# altmotor2.net
KiCad netlist of a schematic drawn in EAGLE
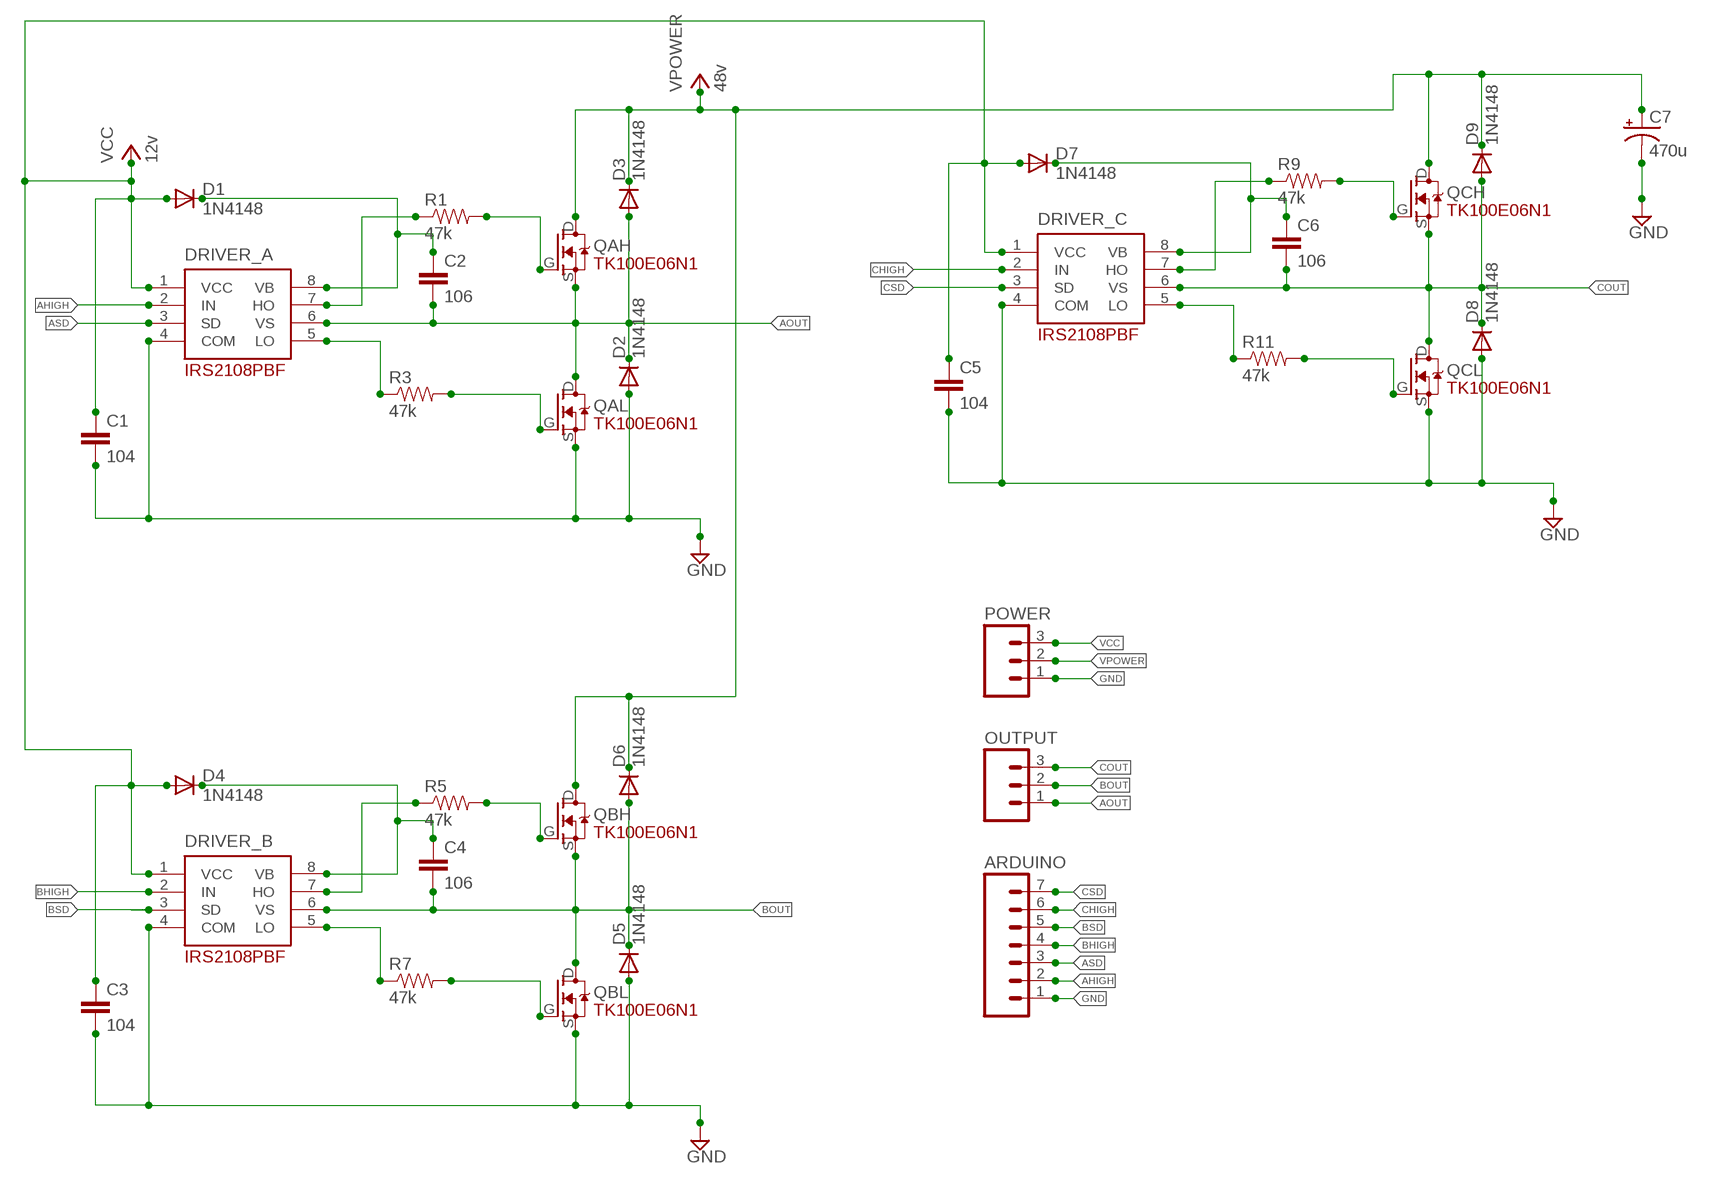
[diagram p0: schematic, sheet 1]

(export (version "E")
  (design (tool "Eeschema 10.0.6"))
  (components
    (comp (ref "ARDUINO")
      (value "M07LONGPADS")
      (footprint "eagle-import:1X07_LONGPADS")
      (libsource (lib "eagle-import") (part "M07LONGPADS"))
    )
    (comp (ref "C1")
      (value "104")
      (footprint "eagle-import:CAP-PTH-5MM")
      (libsource (lib "eagle-import") (part "CAPPTH1"))
    )
    (comp (ref "C2")
      (value "106")
      (footprint "eagle-import:CAP-PTH-5MM")
      (libsource (lib "eagle-import") (part "CAPPTH1"))
    )
    (comp (ref "C3")
      (value "104")
      (footprint "eagle-import:CAP-PTH-5MM")
      (libsource (lib "eagle-import") (part "CAPPTH1"))
    )
    (comp (ref "C4")
      (value "106")
      (footprint "eagle-import:CAP-PTH-5MM")
      (libsource (lib "eagle-import") (part "CAPPTH1"))
    )
    (comp (ref "C5")
      (value "104")
      (footprint "eagle-import:CAP-PTH-5MM")
      (libsource (lib "eagle-import") (part "CAPPTH1"))
    )
    (comp (ref "C6")
      (value "106")
      (footprint "eagle-import:CAP-PTH-5MM")
      (libsource (lib "eagle-import") (part "CAPPTH1"))
    )
    (comp (ref "C7")
      (value "470u")
      (footprint "eagle-import:EB20D")
      (libsource (lib "eagle-import") (part "CPOL-USE10-20"))
    )
    (comp (ref "D1")
      (value "1N4148")
      (footprint "eagle-import:DIODE-1N4001")
      (libsource (lib "eagle-import") (part "DIODEPTH"))
    )
    (comp (ref "D2")
      (value "1N4148")
      (footprint "eagle-import:DIODE-1N4001")
      (libsource (lib "eagle-import") (part "DIODEPTH"))
    )
    (comp (ref "D3")
      (value "1N4148")
      (footprint "eagle-import:DIODE-1N4001")
      (libsource (lib "eagle-import") (part "DIODEPTH"))
    )
    (comp (ref "D4")
      (value "1N4148")
      (footprint "eagle-import:DIODE-1N4001")
      (libsource (lib "eagle-import") (part "DIODEPTH"))
    )
    (comp (ref "D5")
      (value "1N4148")
      (footprint "eagle-import:DIODE-1N4001")
      (libsource (lib "eagle-import") (part "DIODEPTH"))
    )
    (comp (ref "D6")
      (value "1N4148")
      (footprint "eagle-import:DIODE-1N4001")
      (libsource (lib "eagle-import") (part "DIODEPTH"))
    )
    (comp (ref "D7")
      (value "1N4148")
      (footprint "eagle-import:DIODE-1N4001")
      (libsource (lib "eagle-import") (part "DIODEPTH"))
    )
    (comp (ref "D8")
      (value "1N4148")
      (footprint "eagle-import:DIODE-1N4001")
      (libsource (lib "eagle-import") (part "DIODEPTH"))
    )
    (comp (ref "D9")
      (value "1N4148")
      (footprint "eagle-import:DIODE-1N4001")
      (libsource (lib "eagle-import") (part "DIODEPTH"))
    )
    (comp (ref "DRIVER_A")
      (value "IRS2108PBF")
      (footprint "eagle-import:DIL08")
      (libsource (lib "eagle-import") (part "IRS2108PBF"))
    )
    (comp (ref "DRIVER_B")
      (value "IRS2108PBF")
      (footprint "eagle-import:DIL08")
      (libsource (lib "eagle-import") (part "IRS2108PBF"))
    )
    (comp (ref "DRIVER_C")
      (value "IRS2108PBF")
      (footprint "eagle-import:DIL08")
      (libsource (lib "eagle-import") (part "IRS2108PBF"))
    )
    (comp (ref "OUTPUT")
      (value "TBLOCK-3")
      (footprint "eagle-import:TBLOCK-3")
      (libsource (lib "eagle-import") (part "TBLOCK-3"))
    )
    (comp (ref "POWER")
      (value "TBLOCK-3")
      (footprint "eagle-import:TBLOCK-3")
      (libsource (lib "eagle-import") (part "TBLOCK-3"))
    )
    (comp (ref "QAH")
      (value "TK100E06N1")
      (footprint "eagle-import:TO-220-2")
      (libsource (lib "eagle-import") (part "TK100E06N1"))
    )
    (comp (ref "QAL")
      (value "TK100E06N1")
      (footprint "eagle-import:TO-220-2")
      (libsource (lib "eagle-import") (part "TK100E06N1"))
    )
    (comp (ref "QBH")
      (value "TK100E06N1")
      (footprint "eagle-import:TO-220-2")
      (libsource (lib "eagle-import") (part "TK100E06N1"))
    )
    (comp (ref "QBL")
      (value "TK100E06N1")
      (footprint "eagle-import:TO-220-2")
      (libsource (lib "eagle-import") (part "TK100E06N1"))
    )
    (comp (ref "QCH")
      (value "TK100E06N1")
      (footprint "eagle-import:TO-220-2")
      (libsource (lib "eagle-import") (part "TK100E06N1"))
    )
    (comp (ref "QCL")
      (value "TK100E06N1")
      (footprint "eagle-import:TO-220-2")
      (libsource (lib "eagle-import") (part "TK100E06N1"))
    )
    (comp (ref "R1")
      (value "47k")
      (footprint "eagle-import:AXIAL-0.3")
      (libsource (lib "eagle-import") (part "RESISTORAXIAL-0.3"))
    )
    (comp (ref "R3")
      (value "47k")
      (footprint "eagle-import:AXIAL-0.3")
      (libsource (lib "eagle-import") (part "RESISTORAXIAL-0.3"))
    )
    (comp (ref "R5")
      (value "47k")
      (footprint "eagle-import:AXIAL-0.3")
      (libsource (lib "eagle-import") (part "RESISTORAXIAL-0.3"))
    )
    (comp (ref "R7")
      (value "47k")
      (footprint "eagle-import:AXIAL-0.3")
      (libsource (lib "eagle-import") (part "RESISTORAXIAL-0.3"))
    )
    (comp (ref "R9")
      (value "47k")
      (footprint "eagle-import:AXIAL-0.3")
      (libsource (lib "eagle-import") (part "RESISTORAXIAL-0.3"))
    )
    (comp (ref "R11")
      (value "47k")
      (footprint "eagle-import:AXIAL-0.3")
      (libsource (lib "eagle-import") (part "RESISTORAXIAL-0.3"))
    )
  )
  (nets
    (net (code "1") (name "AHIGH") (class "Default")
      (node (ref "ARDUINO") (pin "2") (pinfunction "2_2") (pintype "passive"))
      (node (ref "DRIVER_A") (pin "2") (pinfunction "IN_2") (pintype "input"))
    )
    (net (code "2") (name "AOUT") (class "Default")
      (node (ref "C2") (pin "2") (pinfunction "2_2") (pintype "passive"))
      (node (ref "D2") (pin "C") (pinfunction "C_C") (pintype "passive"))
      (node (ref "D3") (pin "A") (pinfunction "A_A") (pintype "passive"))
      (node (ref "DRIVER_A") (pin "6") (pinfunction "VS_6") (pintype "power_in"))
      (node (ref "OUTPUT") (pin "1") (pinfunction "1_1") (pintype "passive"))
      (node (ref "QAH") (pin "S") (pinfunction "S_S") (pintype "bidirectional"))
      (node (ref "QAL") (pin "D") (pinfunction "D_D") (pintype "bidirectional"))
    )
    (net (code "3") (name "ASD") (class "Default")
      (node (ref "ARDUINO") (pin "3") (pinfunction "3_3") (pintype "passive"))
      (node (ref "DRIVER_A") (pin "3") (pinfunction "SD_3") (pintype "input"))
    )
    (net (code "4") (name "BHIGH") (class "Default")
      (node (ref "ARDUINO") (pin "4") (pinfunction "4_4") (pintype "passive"))
      (node (ref "DRIVER_B") (pin "2") (pinfunction "IN_2") (pintype "input"))
    )
    (net (code "5") (name "BOUT") (class "Default")
      (node (ref "C4") (pin "2") (pinfunction "2_2") (pintype "passive"))
      (node (ref "D5") (pin "C") (pinfunction "C_C") (pintype "passive"))
      (node (ref "D6") (pin "A") (pinfunction "A_A") (pintype "passive"))
      (node (ref "DRIVER_B") (pin "6") (pinfunction "VS_6") (pintype "power_in"))
      (node (ref "OUTPUT") (pin "2") (pinfunction "2_2") (pintype "passive"))
      (node (ref "QBH") (pin "S") (pinfunction "S_S") (pintype "bidirectional"))
      (node (ref "QBL") (pin "D") (pinfunction "D_D") (pintype "bidirectional"))
    )
    (net (code "6") (name "BSD") (class "Default")
      (node (ref "ARDUINO") (pin "5") (pinfunction "5_5") (pintype "passive"))
      (node (ref "DRIVER_B") (pin "3") (pinfunction "SD_3") (pintype "input"))
    )
    (net (code "7") (name "CHIGH") (class "Default")
      (node (ref "ARDUINO") (pin "6") (pinfunction "6_6") (pintype "passive"))
      (node (ref "DRIVER_C") (pin "2") (pinfunction "IN_2") (pintype "input"))
    )
    (net (code "8") (name "COUT") (class "Default")
      (node (ref "C6") (pin "2") (pinfunction "2_2") (pintype "passive"))
      (node (ref "D8") (pin "C") (pinfunction "C_C") (pintype "passive"))
      (node (ref "D9") (pin "A") (pinfunction "A_A") (pintype "passive"))
      (node (ref "DRIVER_C") (pin "6") (pinfunction "VS_6") (pintype "power_in"))
      (node (ref "OUTPUT") (pin "3") (pinfunction "3_3") (pintype "passive"))
      (node (ref "QCH") (pin "S") (pinfunction "S_S") (pintype "bidirectional"))
      (node (ref "QCL") (pin "D") (pinfunction "D_D") (pintype "bidirectional"))
    )
    (net (code "9") (name "CSD") (class "Default")
      (node (ref "ARDUINO") (pin "7") (pinfunction "7_7") (pintype "passive"))
      (node (ref "DRIVER_C") (pin "3") (pinfunction "SD_3") (pintype "input"))
    )
    (net (code "10") (name "GND") (class "Default")
      (node (ref "ARDUINO") (pin "1") (pinfunction "1_1") (pintype "passive"))
      (node (ref "C1") (pin "2") (pinfunction "2_2") (pintype "passive"))
      (node (ref "C3") (pin "2") (pinfunction "2_2") (pintype "passive"))
      (node (ref "C5") (pin "2") (pinfunction "2_2") (pintype "passive"))
      (node (ref "C7") (pin "-") (pinfunction "-_-") (pintype "passive"))
      (node (ref "D2") (pin "A") (pinfunction "A_A") (pintype "passive"))
      (node (ref "D5") (pin "A") (pinfunction "A_A") (pintype "passive"))
      (node (ref "D8") (pin "A") (pinfunction "A_A") (pintype "passive"))
      (node (ref "DRIVER_A") (pin "4") (pinfunction "COM_4") (pintype "input"))
      (node (ref "DRIVER_B") (pin "4") (pinfunction "COM_4") (pintype "input"))
      (node (ref "DRIVER_C") (pin "4") (pinfunction "COM_4") (pintype "input"))
      (node (ref "POWER") (pin "1") (pinfunction "1_1") (pintype "passive"))
      (node (ref "QAL") (pin "S") (pinfunction "S_S") (pintype "bidirectional"))
      (node (ref "QBL") (pin "S") (pinfunction "S_S") (pintype "bidirectional"))
      (node (ref "QCL") (pin "S") (pinfunction "S_S") (pintype "bidirectional"))
    )
    (net (code "11") (name "Net-(DRIVER_A-HO)") (class "Default")
      (node (ref "DRIVER_A") (pin "7") (pinfunction "HO_7") (pintype "power_in"))
      (node (ref "R1") (pin "P$1") (pinfunction "1_P$1") (pintype "passive"))
    )
    (net (code "12") (name "Net-(DRIVER_A-LO)") (class "Default")
      (node (ref "DRIVER_A") (pin "5") (pinfunction "LO_5") (pintype "power_in"))
      (node (ref "R3") (pin "P$1") (pinfunction "1_P$1") (pintype "passive"))
    )
    (net (code "13") (name "Net-(DRIVER_A-VB)") (class "Default")
      (node (ref "C2") (pin "1") (pinfunction "1_1") (pintype "passive"))
      (node (ref "D1") (pin "C") (pinfunction "C_C") (pintype "passive"))
      (node (ref "DRIVER_A") (pin "8") (pinfunction "VB_8") (pintype "power_in"))
    )
    (net (code "14") (name "Net-(DRIVER_B-HO)") (class "Default")
      (node (ref "DRIVER_B") (pin "7") (pinfunction "HO_7") (pintype "power_in"))
      (node (ref "R5") (pin "P$1") (pinfunction "1_P$1") (pintype "passive"))
    )
    (net (code "15") (name "Net-(DRIVER_B-LO)") (class "Default")
      (node (ref "DRIVER_B") (pin "5") (pinfunction "LO_5") (pintype "power_in"))
      (node (ref "R7") (pin "P$1") (pinfunction "1_P$1") (pintype "passive"))
    )
    (net (code "16") (name "Net-(DRIVER_B-VB)") (class "Default")
      (node (ref "C4") (pin "1") (pinfunction "1_1") (pintype "passive"))
      (node (ref "D4") (pin "C") (pinfunction "C_C") (pintype "passive"))
      (node (ref "DRIVER_B") (pin "8") (pinfunction "VB_8") (pintype "power_in"))
    )
    (net (code "17") (name "Net-(DRIVER_C-HO)") (class "Default")
      (node (ref "DRIVER_C") (pin "7") (pinfunction "HO_7") (pintype "power_in"))
      (node (ref "R9") (pin "P$1") (pinfunction "1_P$1") (pintype "passive"))
    )
    (net (code "18") (name "Net-(DRIVER_C-LO)") (class "Default")
      (node (ref "DRIVER_C") (pin "5") (pinfunction "LO_5") (pintype "power_in"))
      (node (ref "R11") (pin "P$1") (pinfunction "1_P$1") (pintype "passive"))
    )
    (net (code "19") (name "Net-(DRIVER_C-VB)") (class "Default")
      (node (ref "C6") (pin "1") (pinfunction "1_1") (pintype "passive"))
      (node (ref "D7") (pin "C") (pinfunction "C_C") (pintype "passive"))
      (node (ref "DRIVER_C") (pin "8") (pinfunction "VB_8") (pintype "power_in"))
    )
    (net (code "20") (name "Net-(R1-2)") (class "Default")
      (node (ref "QAH") (pin "G") (pinfunction "G_G") (pintype "bidirectional"))
      (node (ref "R1") (pin "P$2") (pinfunction "2_P$2") (pintype "passive"))
    )
    (net (code "21") (name "Net-(R3-2)") (class "Default")
      (node (ref "QAL") (pin "G") (pinfunction "G_G") (pintype "bidirectional"))
      (node (ref "R3") (pin "P$2") (pinfunction "2_P$2") (pintype "passive"))
    )
    (net (code "22") (name "Net-(R5-2)") (class "Default")
      (node (ref "QBH") (pin "G") (pinfunction "G_G") (pintype "bidirectional"))
      (node (ref "R5") (pin "P$2") (pinfunction "2_P$2") (pintype "passive"))
    )
    (net (code "23") (name "Net-(R7-2)") (class "Default")
      (node (ref "QBL") (pin "G") (pinfunction "G_G") (pintype "bidirectional"))
      (node (ref "R7") (pin "P$2") (pinfunction "2_P$2") (pintype "passive"))
    )
    (net (code "24") (name "Net-(R9-2)") (class "Default")
      (node (ref "QCH") (pin "G") (pinfunction "G_G") (pintype "bidirectional"))
      (node (ref "R9") (pin "P$2") (pinfunction "2_P$2") (pintype "passive"))
    )
    (net (code "25") (name "Net-(R11-2)") (class "Default")
      (node (ref "QCL") (pin "G") (pinfunction "G_G") (pintype "bidirectional"))
      (node (ref "R11") (pin "P$2") (pinfunction "2_P$2") (pintype "passive"))
    )
    (net (code "26") (name "VCC") (class "Default")
      (node (ref "C1") (pin "1") (pinfunction "1_1") (pintype "passive"))
      (node (ref "C3") (pin "1") (pinfunction "1_1") (pintype "passive"))
      (node (ref "C5") (pin "1") (pinfunction "1_1") (pintype "passive"))
      (node (ref "D1") (pin "A") (pinfunction "A_A") (pintype "passive"))
      (node (ref "D4") (pin "A") (pinfunction "A_A") (pintype "passive"))
      (node (ref "D7") (pin "A") (pinfunction "A_A") (pintype "passive"))
      (node (ref "DRIVER_A") (pin "1") (pinfunction "VCC_1") (pintype "power_in"))
      (node (ref "DRIVER_B") (pin "1") (pinfunction "VCC_1") (pintype "power_in"))
      (node (ref "DRIVER_C") (pin "1") (pinfunction "VCC_1") (pintype "power_in"))
      (node (ref "POWER") (pin "3") (pinfunction "3_3") (pintype "passive"))
    )
    (net (code "27") (name "VPOWER") (class "Default")
      (node (ref "C7") (pin "+") (pinfunction "+_+") (pintype "passive"))
      (node (ref "D3") (pin "C") (pinfunction "C_C") (pintype "passive"))
      (node (ref "D6") (pin "C") (pinfunction "C_C") (pintype "passive"))
      (node (ref "D9") (pin "C") (pinfunction "C_C") (pintype "passive"))
      (node (ref "POWER") (pin "2") (pinfunction "2_2") (pintype "passive"))
      (node (ref "QAH") (pin "D") (pinfunction "D_D") (pintype "bidirectional"))
      (node (ref "QBH") (pin "D") (pinfunction "D_D") (pintype "bidirectional"))
      (node (ref "QCH") (pin "D") (pinfunction "D_D") (pintype "bidirectional"))
    )
  )
)
